# M5-RelayDriver.net
KiCad netlist of a schematic drawn in Altium Designer
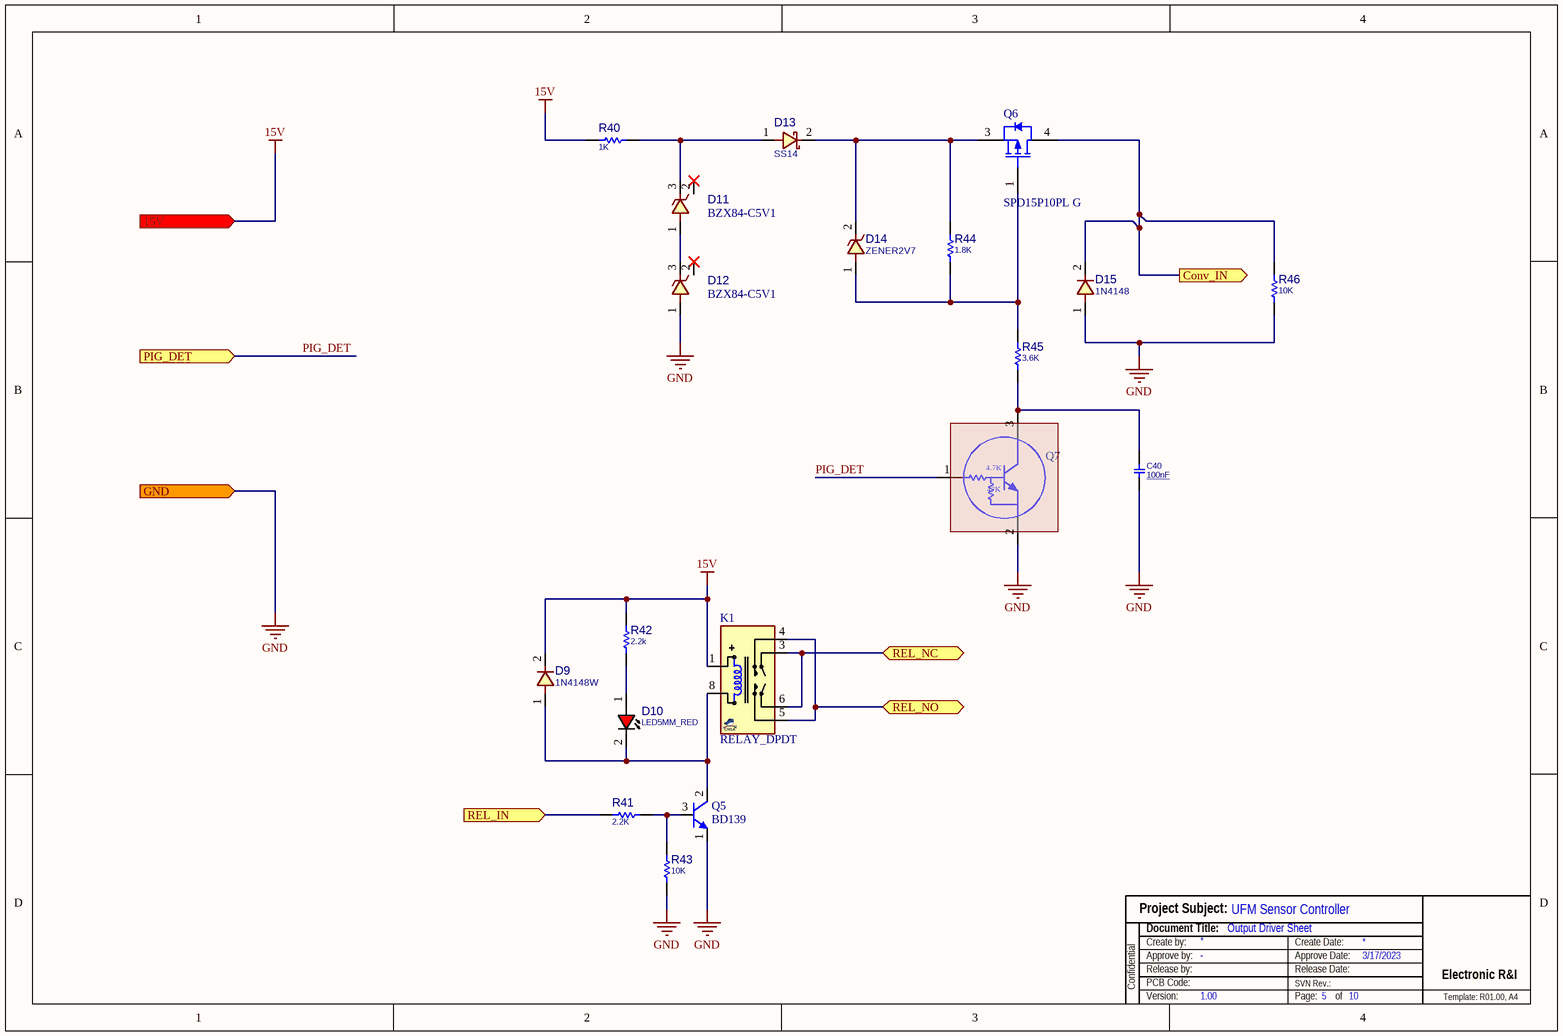
[diagram p0: M5-RelayDriver.SchDoc]

(export (version "E")
  (design (tool "Eeschema 10.0.6"))
  (components
    (comp (ref "C40")
      (value "100nF")
      (footprint "C1206")
      (description "CAP, MLCC, 1nF, 50V, C0G, 10%, 0402")
      (fields (field (name "MANF_P#") "MANF_PART#") (field (name "MANF") "Murata"))
      (libsource (lib "passive_smd") (part "CAP_SMD_MLCC"))
    )
    (comp (ref "D9")
      (value "1N4148W")
      (footprint "D_SOD123W")
      (description "DIODE, FAST SWTICHING, 0.3A, 0.5W")
      (fields (field (name "MANF") "MANF") (field (name "MANF_P#") "1N4148"))
      (libsource (lib "diode") (part "DIODE_SMD_1N4148_SOD80"))
    )
    (comp (ref "D10")
      (value "LED5MM_RED")
      (footprint "LED5MM_RED")
      (description "LED, THD, 5MM, RED")
      (fields (field (name "MANF") "MANF") (field (name "MANF_P#") "MANF_PART#"))
      (libsource (lib "led(diode)") (part "LED_THD_5MM_RED"))
    )
    (comp (ref "D11")
      (value "ZENER2V4")
      (footprint "SOT23_3")
      (description "DIODE, ZENER, 0.25W, 2.4V")
      (fields (field (name "MANF") "NXP") (field (name "MANF_P#") "BZX84-C5V1"))
      (libsource (lib "diode") (part "DIODE_SMD_ZENER_BZX84-C2V4"))
    )
    (comp (ref "D12")
      (value "ZENER2V4")
      (footprint "SOT23_3")
      (description "DIODE, ZENER, 0.25W, 2.4V")
      (fields (field (name "MANF") "NXP") (field (name "MANF_P#") "BZX84-C5V1"))
      (libsource (lib "diode") (part "DIODE_SMD_ZENER_BZX84-C2V4"))
    )
    (comp (ref "D13")
      (value "SS14")
      (footprint "D_SMB")
      (description "DIODE, SCHOTTKY, 40V, 1A")
      (fields (field (name "MANF") "Vishay") (field (name "MANF_P#") "SS14-E3"))
      (libsource (lib "diode") (part "DIODE_SMD_SCHOTTKY_SS14"))
    )
    (comp (ref "D14")
      (value "ZENER2V7")
      (footprint "D0805")
      (description "DIODE, ZENER, 0.2W, 2.7V")
      (fields (field (name "MANF_P#") "MM3Z2V7B") (field (name "MANF") "Fairchild"))
      (libsource (lib "diode") (part "DIODE_SMD_ZENER_MM3Z2V7B"))
    )
    (comp (ref "D15")
      (value "1N4148")
      (footprint "D_AX02_DO35")
      (description "DIODE, FAST SWTICHING, THD")
      (fields (field (name "MANF") "MANF"))
      (libsource (lib "diode") (part "DIODE_THD_1N4148_DO35"))
    )
    (comp (ref "K1")
      (value "RELAY_DPDT")
      (footprint "REL_DPDT_8_2913")
      (description "Relay, DPDT, 8P, 29X13mm, RT2, 400VAC/8A")
      (fields (field (name "MANF") "TE") (field (name "MANF_P#") "RTE24012"))
      (libsource (lib "relay") (part "RELAY_DPST_8_2913_RT2"))
    )
    (comp (ref "Q5")
      (value "BD139")
      (footprint "TO126_3")
      (description "BJT, NPN, 80V, 1.5A")
      (fields (field (name "MANF") "FAIRCHILD"))
      (libsource (lib "transistor_bjt") (part "NPN_BD139_TO126"))
    )
    (comp (ref "Q6")
      (value "SPD15P10PL G")
      (footprint "TO-252 (D-PAK)")
      (description "Transistor-MOSFET,S,P,15A,100V,TO-252")
      (fields (field (name "POWER") "128W"))
      (libsource (lib "Crouse") (part "SPD15P10PL G"))
    )
    (comp (ref "Q7")
      (value "BCR116")
      (footprint "SOT23:SOT23")
      (description "NPN Silicon Digital Transistor")
      (libsource (lib "BCR116") (part "BCR116"))
    )
    (comp (ref "R40")
      (value "1K")
      (footprint "R1206")
      (description "RESISTOR, SMD")
      (libsource (lib "passive_smd") (part "RES_SMD"))
    )
    (comp (ref "R41")
      (value "2.2K")
      (footprint "R1206")
      (description "RESISTOR, SMD")
      (fields (field (name "MANF_P#") "RK73H1ETTP4701F") (field (name "MANF") "KOA SPEER"))
      (libsource (lib "passive") (part "RES_SMD"))
    )
    (comp (ref "R42")
      (value "2.2k")
      (footprint "R1206")
      (description "RESISTOR, SMD")
      (fields (field (name "MANF_P#") "RK73H1ETTP4701F") (field (name "MANF") "KOA SPEER"))
      (libsource (lib "passive") (part "RES_SMD"))
    )
    (comp (ref "R43")
      (value "10K")
      (footprint "R1206")
      (description "RESISTOR, SMD")
      (libsource (lib "passive_smd") (part "RES_SMD"))
    )
    (comp (ref "R44")
      (value "1.8K")
      (footprint "R1206")
      (description "RESISTOR, SMD")
      (libsource (lib "passive_smd") (part "RES_SMD_1206"))
    )
    (comp (ref "R45")
      (value "3.6K")
      (footprint "R1206")
      (description "RESISTOR, SMD")
      (libsource (lib "passive_smd") (part "RES_SMD_1206"))
    )
    (comp (ref "R46")
      (value "10K")
      (footprint "R1206")
      (description "RESISTOR, SMD")
      (libsource (lib "passive_smd") (part "RES_SMD"))
    )
  )
  (nets
    (net (code "1") (name "/Conv_IN") (class "Default")
      (node (ref "D15") (pin "2") (pinfunction "2_2") (pintype "passive"))
      (node (ref "Q6") (pin "4") (pinfunction "D_4") (pintype "passive"))
      (node (ref "R46") (pin "2") (pinfunction "2_2") (pintype "passive"))
    )
    (net (code "2") (name "/PIG_DET") (class "Default")
      (node (ref "Q7") (pin "1") (pinfunction "B_1") (pintype "passive"))
    )
    (net (code "3") (name "/REL_IN") (class "Default")
      (node (ref "R41") (pin "1") (pinfunction "1_1") (pintype "passive"))
    )
    (net (code "4") (name "/REL_NC") (class "Default")
      (node (ref "K1") (pin "3") (pinfunction "COM1_3") (pintype "passive"))
      (node (ref "K1") (pin "6") (pinfunction "COM2_6") (pintype "passive"))
    )
    (net (code "5") (name "/REL_NO") (class "Default")
      (node (ref "K1") (pin "4") (pinfunction "NO1_4") (pintype "passive"))
      (node (ref "K1") (pin "5") (pinfunction "NO2_5") (pintype "passive"))
    )
    (net (code "6") (name "15V") (class "Default")
      (node (ref "D9") (pin "2") (pinfunction "2_2") (pintype "passive"))
      (node (ref "K1") (pin "1") (pinfunction "T1_1") (pintype "passive"))
      (node (ref "R40") (pin "1") (pinfunction "1_1") (pintype "passive"))
      (node (ref "R42") (pin "2") (pinfunction "2_2") (pintype "passive"))
    )
    (net (code "7") (name "GND") (class "Default")
      (node (ref "C40") (pin "1") (pinfunction "1_1") (pintype "passive"))
      (node (ref "D12") (pin "1") (pinfunction "1_1") (pintype "passive"))
      (node (ref "D15") (pin "1") (pinfunction "1_1") (pintype "passive"))
      (node (ref "Q5") (pin "1") (pinfunction "E_1") (pintype "passive"))
      (node (ref "Q7") (pin "2") (pinfunction "E_2") (pintype "passive"))
      (node (ref "R43") (pin "1") (pinfunction "1_1") (pintype "passive"))
      (node (ref "R46") (pin "1") (pinfunction "1_1") (pintype "passive"))
    )
    (net (code "8") (name "Net-(D10-ANODE)") (class "Default")
      (node (ref "D10") (pin "1") (pinfunction "ANODE_1") (pintype "passive"))
      (node (ref "R42") (pin "1") (pinfunction "1_1") (pintype "passive"))
    )
    (net (code "9") (name "Net-(D10-CATHODE)") (class "Default")
      (node (ref "D10") (pin "2") (pinfunction "CATHODE_2") (pintype "passive"))
      (node (ref "D9") (pin "1") (pinfunction "1_1") (pintype "passive"))
      (node (ref "K1") (pin "8") (pinfunction "T2_8") (pintype "passive"))
      (node (ref "Q5") (pin "2") (pinfunction "C_2") (pintype "passive"))
    )
    (net (code "10") (name "Net-(D11-Pad1)") (class "Default")
      (node (ref "D11") (pin "1") (pinfunction "1_1") (pintype "passive"))
      (node (ref "D12") (pin "3") (pinfunction "3_3") (pintype "passive"))
    )
    (net (code "11") (name "Net-(D11-Pad3)") (class "Default")
      (node (ref "D11") (pin "3") (pinfunction "3_3") (pintype "passive"))
      (node (ref "D13") (pin "1") (pinfunction "1_1") (pintype "passive"))
      (node (ref "R40") (pin "2") (pinfunction "2_2") (pintype "passive"))
    )
    (net (code "12") (name "Net-(Q5-B)") (class "Default")
      (node (ref "Q5") (pin "3") (pinfunction "B_3") (pintype "passive"))
      (node (ref "R41") (pin "2") (pinfunction "2_2") (pintype "passive"))
      (node (ref "R43") (pin "2") (pinfunction "2_2") (pintype "passive"))
    )
    (net (code "13") (name "Net-(Q6-G)") (class "Default")
      (node (ref "D14") (pin "1") (pinfunction "1_1") (pintype "passive"))
      (node (ref "Q6") (pin "1") (pinfunction "G_1") (pintype "passive"))
      (node (ref "R44") (pin "1") (pinfunction "1_1") (pintype "passive"))
      (node (ref "R45") (pin "2") (pinfunction "2_2") (pintype "passive"))
    )
    (net (code "14") (name "Net-(Q6-S)") (class "Default")
      (node (ref "D13") (pin "2") (pinfunction "2_2") (pintype "passive"))
      (node (ref "D14") (pin "2") (pinfunction "2_2") (pintype "passive"))
      (node (ref "Q6") (pin "3") (pinfunction "S_3") (pintype "passive"))
      (node (ref "R44") (pin "2") (pinfunction "2_2") (pintype "passive"))
    )
    (net (code "15") (name "Net-(Q7-C)") (class "Default")
      (node (ref "C40") (pin "2") (pinfunction "2_2") (pintype "passive"))
      (node (ref "Q7") (pin "3") (pinfunction "C_3") (pintype "passive"))
      (node (ref "R45") (pin "1") (pinfunction "1_1") (pintype "passive"))
    )
    (net (code "16") (name "unconnected-(D11-Pad2)") (class "Default")
      (node (ref "D11") (pin "2") (pinfunction "2_2") (pintype "passive+no_connect"))
    )
    (net (code "17") (name "unconnected-(D12-Pad2)") (class "Default")
      (node (ref "D12") (pin "2") (pinfunction "2_2") (pintype "passive+no_connect"))
    )
  )
)
